# SWITCHING.net
KiCad netlist of a schematic drawn in Altium Designer
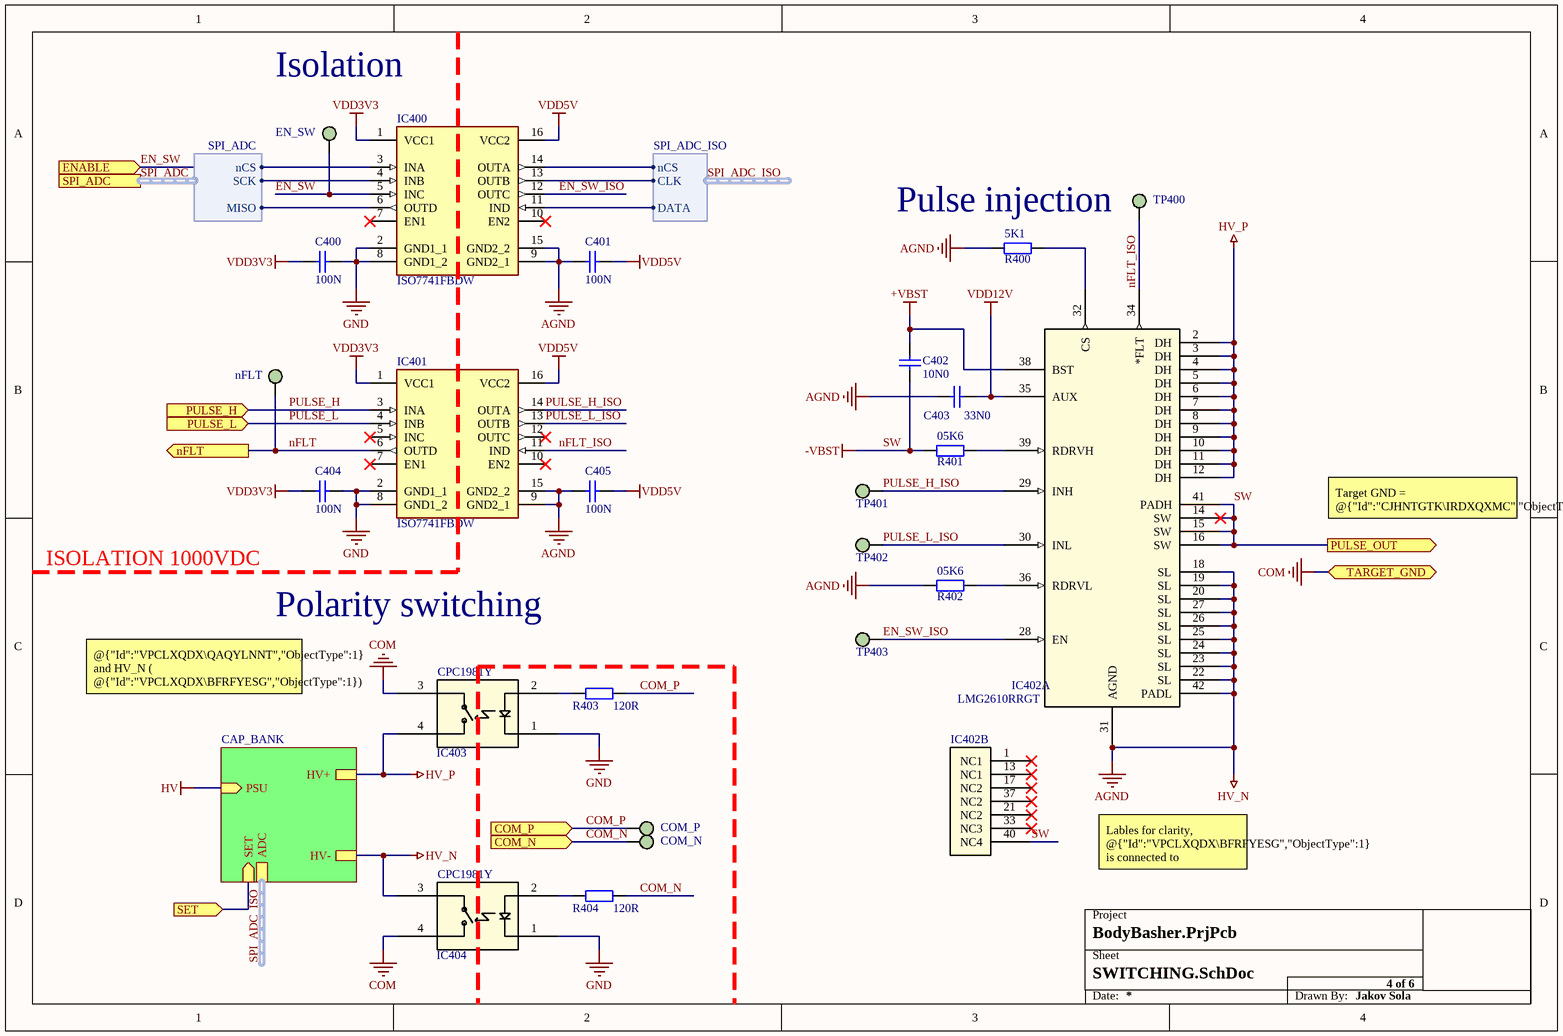
[diagram p0: SWITCHING.SchDoc]

(export (version "E")
  (design (tool "Eeschema 10.0.6"))
  (components
    (comp (ref "C400")
      (value "Cap")
      (footprint "CAPC0603N")
      (fields
        (field (name "VALUE_4C") "100N")
        (field (name "VOLTAGE") "25V")
        (field (name "TOLERANCE") "0.1")
      )
      (libsource (lib "Capacitors") (part "Cap"))
    )
    (comp (ref "C401")
      (value "Cap")
      (footprint "CAPC0603N")
      (fields
        (field (name "VALUE_4C") "100N")
        (field (name "VOLTAGE") "25V")
        (field (name "TOLERANCE") "0.1")
      )
      (libsource (lib "Capacitors") (part "Cap"))
    )
    (comp (ref "C402")
      (value "Cap")
      (footprint "CAPC0603N")
      (fields
        (field (name "VALUE_4C") "10N0")
        (field (name "VOLTAGE") "50V")
        (field (name "TOLERANCE") "0.05")
      )
      (libsource (lib "Capacitors") (part "Cap"))
    )
    (comp (ref "C403")
      (value "Cap")
      (footprint "CAPC0603N")
      (fields
        (field (name "VALUE_4C") "33N0")
        (field (name "VOLTAGE") "50V")
        (field (name "TOLERANCE") "0.1")
      )
      (libsource (lib "Capacitors") (part "Cap"))
    )
    (comp (ref "C404")
      (value "Cap")
      (footprint "CAPC0603N")
      (fields
        (field (name "VALUE_4C") "100N")
        (field (name "VOLTAGE") "25V")
        (field (name "TOLERANCE") "0.1")
      )
      (libsource (lib "Capacitors") (part "Cap"))
    )
    (comp (ref "C405")
      (value "Cap")
      (footprint "CAPC0603N")
      (fields
        (field (name "VALUE_4C") "100N")
        (field (name "VOLTAGE") "25V")
        (field (name "TOLERANCE") "0.1")
      )
      (libsource (lib "Capacitors") (part "Cap"))
    )
    (comp (ref "COM_N") (value "TP") (footprint "TP") (libsource (lib "") (part "TP_1")))
    (comp (ref "COM_P") (value "TP") (footprint "TP") (libsource (lib "") (part "TP_1")))
    (comp (ref "EN_SW") (value "TP") (footprint "TP") (libsource (lib "Other_passive") (part "TP")))
    (comp (ref "IC400")
      (value "ISO7741FBDW")
      (footprint "SOIC16")
      (libsource (lib "Integrated_circuits") (part "ISO7741FBDW"))
    )
    (comp (ref "IC401")
      (value "ISO7741FBDW")
      (footprint "SOIC16")
      (libsource (lib "Integrated_circuits") (part "ISO7741FBDW"))
    )
    (comp (ref "IC402")
      (value "LMG2610RRGT")
      (footprint "XLMG2610RRGT")
      (libsource (lib "Integrated_circuits") (part "LMG2610RRGT"))
    )
    (comp (ref "IC403")
      (value "SSR_SPST_NO")
      (footprint "CPC1981Y")
      (fields (field (name "MANUFCODE") "CPC1981Y"))
      (libsource (lib "Integrated_circuits") (part "SSR_SPST_NO"))
    )
    (comp (ref "IC404")
      (value "SSR_SPST_NO")
      (footprint "CPC1981Y")
      (fields (field (name "MANUFCODE") "CPC1981Y"))
      (libsource (lib "Integrated_circuits") (part "SSR_SPST_NO"))
    )
    (comp (ref "nFLT") (value "TP") (footprint "TP") (libsource (lib "Other_passive") (part "TP")))
    (comp (ref "R400")
      (value "5K1")
      (footprint "RESC0603N")
      (description "Resistor")
      (fields (field (name "POWER") "0.063W") (field (name "TOLERANCE") "1%"))
      (libsource (lib "Resistors") (part "Res"))
    )
    (comp (ref "R401")
      (value "Res")
      (footprint "RESC0603N")
      (description "Resistor")
      (fields
        (field (name "VALUE_4C") "05K6")
        (field (name "POWER") "0.063W")
        (field (name "TOLERANCE") "1%")
      )
      (libsource (lib "Resistors") (part "Res"))
    )
    (comp (ref "R402")
      (value "Res")
      (footprint "RESC0603N")
      (description "Resistor")
      (fields
        (field (name "VALUE_4C") "05K6")
        (field (name "POWER") "0.063W")
        (field (name "TOLERANCE") "1%")
      )
      (libsource (lib "Resistors") (part "Res"))
    )
    (comp (ref "R403")
      (value "Res")
      (footprint "RESC0603N")
      (description "Resistor")
      (fields (field (name "VALUE_4C") "120R") (field (name "POWER") "0.1W") (field (name "TOLERANCE") "1%"))
      (libsource (lib "Resistors") (part "Res"))
    )
    (comp (ref "R404")
      (value "Res")
      (footprint "RESC0603N")
      (description "Resistor")
      (fields (field (name "VALUE_4C") "120R") (field (name "POWER") "0.1W") (field (name "TOLERANCE") "1%"))
      (libsource (lib "Resistors") (part "Res"))
    )
    (comp (ref "TP400") (value "TP") (footprint "TP") (libsource (lib "") (part "TP_1")))
    (comp (ref "TP401") (value "TP") (footprint "TP") (libsource (lib "") (part "TP_1")))
    (comp (ref "TP402") (value "TP") (footprint "TP") (libsource (lib "") (part "TP_1")))
    (comp (ref "TP403") (value "TP") (footprint "TP") (libsource (lib "") (part "TP_1")))
  )
  (nets
    (net (code "4") (name "+VBST") (class "Default")
      (node (ref "C402") (pin "2") (pinfunction "2_2") (pintype "passive"))
      (node (ref "IC402") (pin "38") (pinfunction "BST_38") (pintype "power_in"))
    )
    (net (code "5") (name "-VBST") (class "Default")
      (node (ref "C402") (pin "1") (pinfunction "1_1") (pintype "passive"))
      (node (ref "IC402") (pin "14") (pinfunction "SW_14") (pintype "power_in"))
      (node (ref "IC402") (pin "15") (pinfunction "SW_15") (pintype "power_in"))
      (node (ref "IC402") (pin "16") (pinfunction "SW_16") (pintype "power_in"))
      (node (ref "IC402") (pin "40") (pinfunction "NC4_40") (pintype "passive"))
      (node (ref "IC402") (pin "41") (pinfunction "PADH_41") (pintype "power_in"))
      (node (ref "R401") (pin "1") (pinfunction "1_1") (pintype "passive"))
    )
    (net (code "6") (name "/CLK") (class "Default")
      (node (ref "IC400") (pin "13") (pinfunction "OUTB_13") (pintype "output"))
    )
    (net (code "7") (name "/COM_N") (class "Default")
      (node (ref "COM_N") (pin "TP") (pinfunction "TP_TP") (pintype "passive"))
      (node (ref "R404") (pin "2") (pinfunction "2_2") (pintype "passive"))
    )
    (net (code "8") (name "/COM_P") (class "Default")
      (node (ref "COM_P") (pin "TP") (pinfunction "TP_TP") (pintype "passive"))
      (node (ref "R403") (pin "2") (pinfunction "2_2") (pintype "passive"))
    )
    (net (code "9") (name "/DATA") (class "Default")
      (node (ref "IC400") (pin "11") (pinfunction "IND_11") (pintype "input"))
    )
    (net (code "10") (name "/EN_SW") (class "Default")
      (node (ref "EN_SW") (pin "TP") (pinfunction "TP_TP") (pintype "passive"))
      (node (ref "IC400") (pin "5") (pinfunction "INC_5") (pintype "input"))
    )
    (net (code "11") (name "/EN_SW_ISO") (class "Default")
      (node (ref "IC400") (pin "12") (pinfunction "OUTC_12") (pintype "output"))
      (node (ref "IC402") (pin "28") (pinfunction "EN_28") (pintype "input"))
      (node (ref "TP403") (pin "TP") (pinfunction "TP_TP") (pintype "passive"))
    )
    (net (code "12") (name "/MISO") (class "Default")
      (node (ref "IC400") (pin "6") (pinfunction "OUTD_6") (pintype "output"))
    )
    (net (code "13") (name "/PULSE_H") (class "Default")
      (node (ref "IC401") (pin "3") (pinfunction "INA_3") (pintype "input"))
    )
    (net (code "14") (name "/PULSE_H_ISO") (class "Default")
      (node (ref "IC401") (pin "14") (pinfunction "OUTA_14") (pintype "output"))
      (node (ref "IC402") (pin "29") (pinfunction "INH_29") (pintype "input"))
      (node (ref "TP401") (pin "TP") (pinfunction "TP_TP") (pintype "passive"))
    )
    (net (code "15") (name "/PULSE_L") (class "Default")
      (node (ref "IC401") (pin "4") (pinfunction "INB_4") (pintype "input"))
    )
    (net (code "16") (name "/PULSE_L_ISO") (class "Default")
      (node (ref "IC401") (pin "13") (pinfunction "OUTB_13") (pintype "output"))
      (node (ref "IC402") (pin "30") (pinfunction "INL_30") (pintype "input"))
      (node (ref "TP402") (pin "TP") (pinfunction "TP_TP") (pintype "passive"))
    )
    (net (code "17") (name "/SCK") (class "Default")
      (node (ref "IC400") (pin "4") (pinfunction "INB_4") (pintype "input"))
    )
    (net (code "21") (name "/nFLT") (class "Default")
      (node (ref "IC401") (pin "6") (pinfunction "OUTD_6") (pintype "output"))
      (node (ref "nFLT") (pin "TP") (pinfunction "TP_TP") (pintype "passive"))
    )
    (net (code "22") (name "/nFLT_ISO") (class "Default")
      (node (ref "IC401") (pin "11") (pinfunction "IND_11") (pintype "input"))
      (node (ref "IC402") (pin "34") (pinfunction "*FLT_34") (pintype "output"))
      (node (ref "TP400") (pin "TP") (pinfunction "TP_TP") (pintype "passive"))
    )
    (net (code "24") (name "AGND") (class "Default")
      (node (ref "C401") (pin "2") (pinfunction "2_2") (pintype "passive"))
      (node (ref "C403") (pin "1") (pinfunction "1_1") (pintype "passive"))
      (node (ref "C405") (pin "2") (pinfunction "2_2") (pintype "passive"))
      (node (ref "IC400") (pin "15") (pinfunction "GND2_2_15") (pintype "passive"))
      (node (ref "IC400") (pin "9") (pinfunction "GND2_1_9") (pintype "passive"))
      (node (ref "IC401") (pin "15") (pinfunction "GND2_2_15") (pintype "passive"))
      (node (ref "IC401") (pin "9") (pinfunction "GND2_1_9") (pintype "passive"))
      (node (ref "IC402") (pin "18") (pinfunction "SL_18") (pintype "power_in"))
      (node (ref "IC402") (pin "19") (pinfunction "SL_19") (pintype "power_in"))
      (node (ref "IC402") (pin "20") (pinfunction "SL_20") (pintype "power_in"))
      (node (ref "IC402") (pin "22") (pinfunction "SL_22") (pintype "power_in"))
      (node (ref "IC402") (pin "23") (pinfunction "SL_23") (pintype "power_in"))
      (node (ref "IC402") (pin "24") (pinfunction "SL_24") (pintype "power_in"))
      (node (ref "IC402") (pin "25") (pinfunction "SL_25") (pintype "power_in"))
      (node (ref "IC402") (pin "26") (pinfunction "SL_26") (pintype "power_in"))
      (node (ref "IC402") (pin "27") (pinfunction "SL_27") (pintype "power_in"))
      (node (ref "IC402") (pin "31") (pinfunction "AGND_31") (pintype "power_in"))
      (node (ref "IC402") (pin "42") (pinfunction "PADL_42") (pintype "power_in"))
      (node (ref "IC404") (pin "3") (pinfunction "NOCL1_3") (pintype "passive"))
      (node (ref "R400") (pin "1") (pinfunction "1_1") (pintype "passive"))
      (node (ref "R402") (pin "1") (pinfunction "1_1") (pintype "passive"))
    )
    (net (code "25") (name "COM") (class "Default")
      (node (ref "IC403") (pin "3") (pinfunction "NOCL1_3") (pintype "passive"))
      (node (ref "IC404") (pin "4") (pinfunction "NOOP2_4") (pintype "passive"))
    )
    (net (code "26") (name "GND") (class "Default")
      (node (ref "C400") (pin "1") (pinfunction "1_1") (pintype "passive"))
      (node (ref "C404") (pin "1") (pinfunction "1_1") (pintype "passive"))
      (node (ref "IC400") (pin "2") (pinfunction "GND1_1_2") (pintype "passive"))
      (node (ref "IC400") (pin "8") (pinfunction "GND1_2_8") (pintype "passive"))
      (node (ref "IC401") (pin "2") (pinfunction "GND1_1_2") (pintype "passive"))
      (node (ref "IC401") (pin "8") (pinfunction "GND1_2_8") (pintype "passive"))
      (node (ref "IC403") (pin "1") (pinfunction "-_1") (pintype "passive"))
      (node (ref "IC404") (pin "1") (pinfunction "-_1") (pintype "passive"))
    )
    (net (code "28") (name "HV_P") (class "Default")
      (node (ref "IC402") (pin "10") (pinfunction "DH_10") (pintype "power_in"))
      (node (ref "IC402") (pin "11") (pinfunction "DH_11") (pintype "power_in"))
      (node (ref "IC402") (pin "12") (pinfunction "DH_12") (pintype "power_in"))
      (node (ref "IC402") (pin "2") (pinfunction "DH_2") (pintype "power_in"))
      (node (ref "IC402") (pin "3") (pinfunction "DH_3") (pintype "power_in"))
      (node (ref "IC402") (pin "4") (pinfunction "DH_4") (pintype "power_in"))
      (node (ref "IC402") (pin "5") (pinfunction "DH_5") (pintype "power_in"))
      (node (ref "IC402") (pin "6") (pinfunction "DH_6") (pintype "power_in"))
      (node (ref "IC402") (pin "7") (pinfunction "DH_7") (pintype "power_in"))
      (node (ref "IC402") (pin "8") (pinfunction "DH_8") (pintype "power_in"))
      (node (ref "IC402") (pin "9") (pinfunction "DH_9") (pintype "power_in"))
      (node (ref "IC403") (pin "4") (pinfunction "NOOP2_4") (pintype "passive"))
    )
    (net (code "29") (name "Net-(IC402A-CS)") (class "Default")
      (node (ref "IC402") (pin "32") (pinfunction "CS_32") (pintype "output"))
      (node (ref "R400") (pin "2") (pinfunction "2_2") (pintype "passive"))
    )
    (net (code "30") (name "Net-(IC402A-RDRVH)") (class "Default")
      (node (ref "IC402") (pin "39") (pinfunction "RDRVH_39") (pintype "input"))
      (node (ref "R401") (pin "2") (pinfunction "2_2") (pintype "passive"))
    )
    (net (code "31") (name "Net-(IC402A-RDRVL)") (class "Default")
      (node (ref "IC402") (pin "36") (pinfunction "RDRVL_36") (pintype "input"))
      (node (ref "R402") (pin "2") (pinfunction "2_2") (pintype "passive"))
    )
    (net (code "32") (name "Net-(IC403-+)") (class "Default")
      (node (ref "IC403") (pin "2") (pinfunction "+_2") (pintype "passive"))
      (node (ref "R403") (pin "1") (pinfunction "1_1") (pintype "passive"))
    )
    (net (code "33") (name "Net-(IC404-+)") (class "Default")
      (node (ref "IC404") (pin "2") (pinfunction "+_2") (pintype "passive"))
      (node (ref "R404") (pin "1") (pinfunction "1_1") (pintype "passive"))
    )
    (net (code "34") (name "VDD3V3") (class "Default")
      (node (ref "C400") (pin "2") (pinfunction "2_2") (pintype "passive"))
      (node (ref "C404") (pin "2") (pinfunction "2_2") (pintype "passive"))
      (node (ref "IC400") (pin "1") (pinfunction "VCC1_1") (pintype "passive"))
      (node (ref "IC401") (pin "1") (pinfunction "VCC1_1") (pintype "passive"))
    )
    (net (code "35") (name "VDD5V") (class "Default")
      (node (ref "C401") (pin "1") (pinfunction "1_1") (pintype "passive"))
      (node (ref "C405") (pin "1") (pinfunction "1_1") (pintype "passive"))
      (node (ref "IC400") (pin "16") (pinfunction "VCC2_16") (pintype "passive"))
      (node (ref "IC401") (pin "16") (pinfunction "VCC2_16") (pintype "passive"))
    )
    (net (code "36") (name "VDD12V") (class "Default")
      (node (ref "C403") (pin "2") (pinfunction "2_2") (pintype "passive"))
      (node (ref "IC402") (pin "35") (pinfunction "AUX_35") (pintype "power_in"))
    )
    (net (code "37") (name "unconnected-(IC400-EN1-Pad7)") (class "Default")
      (node (ref "IC400") (pin "7") (pinfunction "EN1_7") (pintype "passive+no_connect"))
    )
    (net (code "38") (name "unconnected-(IC400-EN2-Pad10)") (class "Default")
      (node (ref "IC400") (pin "10") (pinfunction "EN2_10") (pintype "passive+no_connect"))
    )
    (net (code "39") (name "unconnected-(IC400-INA-Pad3)") (class "Default")
      (node (ref "IC400") (pin "3") (pinfunction "INA_3") (pintype "input"))
    )
    (net (code "40") (name "unconnected-(IC400-OUTA-Pad14)") (class "Default")
      (node (ref "IC400") (pin "14") (pinfunction "OUTA_14") (pintype "output"))
    )
    (net (code "41") (name "unconnected-(IC401-EN1-Pad7)") (class "Default")
      (node (ref "IC401") (pin "7") (pinfunction "EN1_7") (pintype "passive+no_connect"))
    )
    (net (code "42") (name "unconnected-(IC401-EN2-Pad10)") (class "Default")
      (node (ref "IC401") (pin "10") (pinfunction "EN2_10") (pintype "passive+no_connect"))
    )
    (net (code "43") (name "unconnected-(IC401-INC-Pad5)") (class "Default")
      (node (ref "IC401") (pin "5") (pinfunction "INC_5") (pintype "input+no_connect"))
    )
    (net (code "44") (name "unconnected-(IC401-OUTC-Pad12)") (class "Default")
      (node (ref "IC401") (pin "12") (pinfunction "OUTC_12") (pintype "output+no_connect"))
    )
    (net (code "45") (name "unconnected-(IC402B-NC1-Pad1)") (class "Default")
      (node (ref "IC402") (pin "1") (pinfunction "NC1_1") (pintype "passive+no_connect"))
    )
    (net (code "46") (name "unconnected-(IC402B-NC1-Pad13)") (class "Default")
      (node (ref "IC402") (pin "13") (pinfunction "NC1_13") (pintype "passive+no_connect"))
    )
    (net (code "47") (name "unconnected-(IC402B-NC2-Pad17)") (class "Default")
      (node (ref "IC402") (pin "17") (pinfunction "NC2_17") (pintype "passive+no_connect"))
    )
    (net (code "48") (name "unconnected-(IC402B-NC2-Pad21)") (class "Default")
      (node (ref "IC402") (pin "21") (pinfunction "NC2_21") (pintype "passive+no_connect"))
    )
    (net (code "49") (name "unconnected-(IC402B-NC2-Pad37)") (class "Default")
      (node (ref "IC402") (pin "37") (pinfunction "NC2_37") (pintype "passive+no_connect"))
    )
    (net (code "50") (name "unconnected-(IC402B-NC3-Pad33)") (class "Default")
      (node (ref "IC402") (pin "33") (pinfunction "NC3_33") (pintype "passive+no_connect"))
    )
  )
)
